# decoupling.net
KiCad netlist of a schematic drawn in Altium Designer
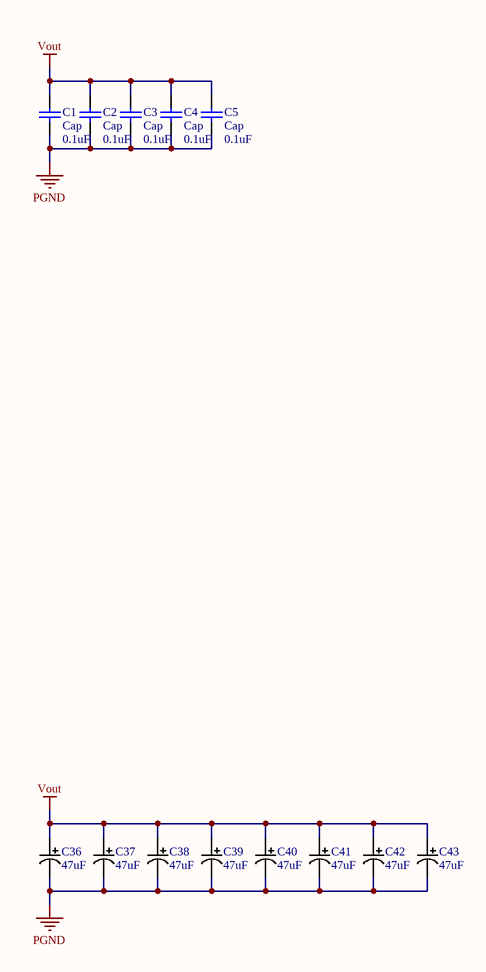
[diagram p0: decoupling.SchDoc]

(export (version "E")
  (design (tool "Eeschema 10.0.6"))
  (components
    (comp (ref "C1")
      (value "Cap")
      (footprint "C0603")
      (description "Capacitor")
      (fields (field (name "ALTIUM_VALUE") "0.1uF") (field (name "PUBLISHER") "Altium Limited"))
      (libsource (lib "Schlib1") (part "Cap"))
    )
    (comp (ref "C2")
      (value "Cap")
      (footprint "C0603")
      (description "Capacitor")
      (fields (field (name "ALTIUM_VALUE") "0.1uF") (field (name "PUBLISHER") "Altium Limited"))
      (libsource (lib "Schlib1") (part "Cap"))
    )
    (comp (ref "C3")
      (value "Cap")
      (footprint "C0603")
      (description "Capacitor")
      (fields (field (name "ALTIUM_VALUE") "0.1uF") (field (name "PUBLISHER") "Altium Limited"))
      (libsource (lib "Schlib1") (part "Cap"))
    )
    (comp (ref "C4")
      (value "Cap")
      (footprint "C0603")
      (description "Capacitor")
      (fields (field (name "ALTIUM_VALUE") "0.1uF") (field (name "PUBLISHER") "Altium Limited"))
      (libsource (lib "Schlib1") (part "Cap"))
    )
    (comp (ref "C5")
      (value "Cap")
      (footprint "C0603")
      (description "Capacitor")
      (fields (field (name "ALTIUM_VALUE") "0.1uF") (field (name "PUBLISHER") "Altium Limited"))
      (libsource (lib "Schlib1") (part "Cap"))
    )
    (comp (ref "C36")
      (value "47uF")
      (footprint "CAP_PC_10X10")
      (description "CAP ALUM POLY 47UF 20% 80V SMD")
      (fields
        (field (name "MANUFACTURER_PART_NUMBER") "KEMET")
        (field (name "MANUFACTURER PART NUMBER") "A767MU476M1KLAE040")
        (field (name "COPYRIGHT") "Copyright (C) 2018 Accelerated Designs. All rights reserved")
      )
      (libsource (lib "Schlib1") (part "A767MU476M1KLAE040"))
    )
    (comp (ref "C37")
      (value "47uF")
      (footprint "CAP_PC_10X10")
      (description "CAP ALUM POLY 47UF 20% 80V SMD")
      (fields
        (field (name "MANUFACTURER_PART_NUMBER") "KEMET")
        (field (name "MANUFACTURER PART NUMBER") "A767MU476M1KLAE040")
        (field (name "COPYRIGHT") "Copyright (C) 2018 Accelerated Designs. All rights reserved")
      )
      (libsource (lib "Schlib1") (part "A767MU476M1KLAE040"))
    )
    (comp (ref "C38")
      (value "47uF")
      (footprint "CAP_PC_10X10")
      (description "CAP ALUM POLY 47UF 20% 80V SMD")
      (fields
        (field (name "MANUFACTURER_PART_NUMBER") "KEMET")
        (field (name "MANUFACTURER PART NUMBER") "A767MU476M1KLAE040")
        (field (name "COPYRIGHT") "Copyright (C) 2018 Accelerated Designs. All rights reserved")
      )
      (libsource (lib "Schlib1") (part "A767MU476M1KLAE040"))
    )
    (comp (ref "C39")
      (value "47uF")
      (footprint "CAP_PC_10X10")
      (description "CAP ALUM POLY 47UF 20% 80V SMD")
      (fields
        (field (name "MANUFACTURER_PART_NUMBER") "KEMET")
        (field (name "MANUFACTURER PART NUMBER") "A767MU476M1KLAE040")
        (field (name "COPYRIGHT") "Copyright (C) 2018 Accelerated Designs. All rights reserved")
      )
      (libsource (lib "Schlib1") (part "A767MU476M1KLAE040"))
    )
    (comp (ref "C40")
      (value "47uF")
      (footprint "CAP_PC_10X10")
      (description "CAP ALUM POLY 47UF 20% 80V SMD")
      (fields
        (field (name "MANUFACTURER_PART_NUMBER") "KEMET")
        (field (name "MANUFACTURER PART NUMBER") "A767MU476M1KLAE040")
        (field (name "COPYRIGHT") "Copyright (C) 2018 Accelerated Designs. All rights reserved")
      )
      (libsource (lib "Schlib1") (part "A767MU476M1KLAE040"))
    )
    (comp (ref "C41")
      (value "47uF")
      (footprint "CAP_PC_10X10")
      (description "CAP ALUM POLY 47UF 20% 80V SMD")
      (fields
        (field (name "MANUFACTURER_PART_NUMBER") "KEMET")
        (field (name "MANUFACTURER PART NUMBER") "A767MU476M1KLAE040")
        (field (name "COPYRIGHT") "Copyright (C) 2018 Accelerated Designs. All rights reserved")
      )
      (libsource (lib "Schlib1") (part "A767MU476M1KLAE040"))
    )
    (comp (ref "C42")
      (value "47uF")
      (footprint "CAP_PC_10X10")
      (description "CAP ALUM POLY 47UF 20% 80V SMD")
      (fields
        (field (name "MANUFACTURER_PART_NUMBER") "KEMET")
        (field (name "MANUFACTURER PART NUMBER") "A767MU476M1KLAE040")
        (field (name "COPYRIGHT") "Copyright (C) 2018 Accelerated Designs. All rights reserved")
      )
      (libsource (lib "Schlib1") (part "A767MU476M1KLAE040"))
    )
    (comp (ref "C43")
      (value "47uF")
      (footprint "CAP_PC_10X10")
      (description "CAP ALUM POLY 47UF 20% 80V SMD")
      (fields
        (field (name "MANUFACTURER_PART_NUMBER") "KEMET")
        (field (name "MANUFACTURER PART NUMBER") "A767MU476M1KLAE040")
        (field (name "COPYRIGHT") "Copyright (C) 2018 Accelerated Designs. All rights reserved")
      )
      (libsource (lib "Schlib1") (part "A767MU476M1KLAE040"))
    )
  )
  (nets
    (net (code "1") (name "PGND") (class "Default")
      (node (ref "C1") (pin "1") (pinfunction "1_1") (pintype "passive"))
      (node (ref "C2") (pin "1") (pinfunction "1_1") (pintype "passive"))
      (node (ref "C3") (pin "1") (pinfunction "1_1") (pintype "passive"))
      (node (ref "C36") (pin "2") (pinfunction "2_2") (pintype "passive"))
      (node (ref "C37") (pin "2") (pinfunction "2_2") (pintype "passive"))
      (node (ref "C38") (pin "2") (pinfunction "2_2") (pintype "passive"))
      (node (ref "C39") (pin "2") (pinfunction "2_2") (pintype "passive"))
      (node (ref "C4") (pin "1") (pinfunction "1_1") (pintype "passive"))
      (node (ref "C40") (pin "2") (pinfunction "2_2") (pintype "passive"))
      (node (ref "C41") (pin "2") (pinfunction "2_2") (pintype "passive"))
      (node (ref "C42") (pin "2") (pinfunction "2_2") (pintype "passive"))
      (node (ref "C43") (pin "2") (pinfunction "2_2") (pintype "passive"))
      (node (ref "C5") (pin "1") (pinfunction "1_1") (pintype "passive"))
    )
    (net (code "2") (name "Vout") (class "Default")
      (node (ref "C1") (pin "2") (pinfunction "2_2") (pintype "passive"))
      (node (ref "C2") (pin "2") (pinfunction "2_2") (pintype "passive"))
      (node (ref "C3") (pin "2") (pinfunction "2_2") (pintype "passive"))
      (node (ref "C36") (pin "1") (pinfunction "1_1") (pintype "passive"))
      (node (ref "C37") (pin "1") (pinfunction "1_1") (pintype "passive"))
      (node (ref "C38") (pin "1") (pinfunction "1_1") (pintype "passive"))
      (node (ref "C39") (pin "1") (pinfunction "1_1") (pintype "passive"))
      (node (ref "C4") (pin "2") (pinfunction "2_2") (pintype "passive"))
      (node (ref "C40") (pin "1") (pinfunction "1_1") (pintype "passive"))
      (node (ref "C41") (pin "1") (pinfunction "1_1") (pintype "passive"))
      (node (ref "C42") (pin "1") (pinfunction "1_1") (pintype "passive"))
      (node (ref "C43") (pin "1") (pinfunction "1_1") (pintype "passive"))
      (node (ref "C5") (pin "2") (pinfunction "2_2") (pintype "passive"))
    )
  )
)
